# pmod-level-conv-vqfn.net
KiCad netlist of a schematic drawn in EAGLE
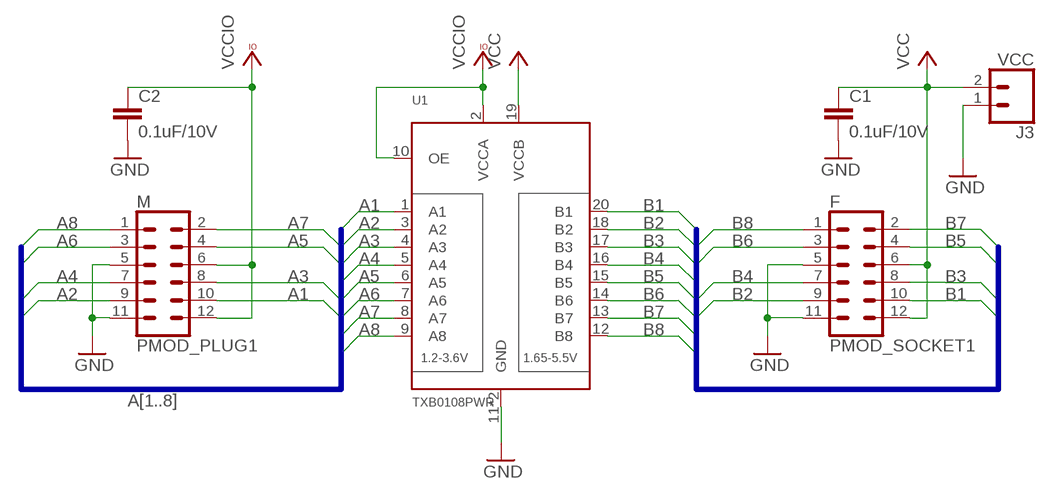
[diagram p0: schematic, sheet 1]

(export (version "E")
  (design (tool "Eeschema 10.0.6"))
  (components
    (comp (ref "C1")
      (value "0.1uF/10V")
      (footprint "eagle-import:C0603K")
      (libsource (lib "eagle-import") (part "C-EUC0603K"))
    )
    (comp (ref "C2")
      (value "0.1uF/10V")
      (footprint "eagle-import:C0603K")
      (libsource (lib "eagle-import") (part "C-EUC0603K"))
    )
    (comp (ref "F")
      (value "PMOD_SOCKET1")
      (footprint "eagle-import:2X6_SMD_RA_SOCKET")
      (libsource (lib "eagle-import") (part "CONN_06X2SMD_RA_SOCKET"))
    )
    (comp (ref "J3")
      (value "VCC")
      (footprint "eagle-import:JST-2-SMD")
      (libsource (lib "eagle-import") (part "CONN_02-JST-2MM-SMT"))
    )
    (comp (ref "M")
      (value "PMOD_PLUG1")
      (footprint "eagle-import:2X6_SMD_RA_PLUG")
      (libsource (lib "eagle-import") (part "CONN_06X2SMD_RA_PLUG"))
    )
    (comp (ref "U1")
      (value "TXB0108PWR")
      (footprint "eagle-import:VQFN-20")
      (libsource (lib "eagle-import") (part "TXB0108PWRVQFN20"))
    )
  )
  (nets
    (net (code "1") (name "/A1") (class "Default")
      (node (ref "M") (pin "10") (pinfunction "10_10") (pintype "passive"))
      (node (ref "U1") (pin "1") (pinfunction "A1_1") (pintype "bidirectional"))
    )
    (net (code "2") (name "/A2") (class "Default")
      (node (ref "M") (pin "9") (pinfunction "9_9") (pintype "passive"))
      (node (ref "U1") (pin "3") (pinfunction "A2_3") (pintype "bidirectional"))
    )
    (net (code "3") (name "/A3") (class "Default")
      (node (ref "M") (pin "8") (pinfunction "8_8") (pintype "passive"))
      (node (ref "U1") (pin "4") (pinfunction "A3_4") (pintype "bidirectional"))
    )
    (net (code "4") (name "/A4") (class "Default")
      (node (ref "M") (pin "7") (pinfunction "7_7") (pintype "passive"))
      (node (ref "U1") (pin "5") (pinfunction "A4_5") (pintype "bidirectional"))
    )
    (net (code "5") (name "/A5") (class "Default")
      (node (ref "M") (pin "4") (pinfunction "4_4") (pintype "passive"))
      (node (ref "U1") (pin "6") (pinfunction "A5_6") (pintype "bidirectional"))
    )
    (net (code "6") (name "/A6") (class "Default")
      (node (ref "M") (pin "3") (pinfunction "3_3") (pintype "passive"))
      (node (ref "U1") (pin "7") (pinfunction "A6_7") (pintype "bidirectional"))
    )
    (net (code "7") (name "/A7") (class "Default")
      (node (ref "M") (pin "2") (pinfunction "2_2") (pintype "passive"))
      (node (ref "U1") (pin "8") (pinfunction "A7_8") (pintype "bidirectional"))
    )
    (net (code "8") (name "/A8") (class "Default")
      (node (ref "M") (pin "1") (pinfunction "1_1") (pintype "passive"))
      (node (ref "U1") (pin "9") (pinfunction "A8_9") (pintype "bidirectional"))
    )
    (net (code "10") (name "/B1") (class "Default")
      (node (ref "F") (pin "10") (pinfunction "10_10") (pintype "passive"))
      (node (ref "U1") (pin "20") (pinfunction "B1_20") (pintype "bidirectional"))
    )
    (net (code "11") (name "/B2") (class "Default")
      (node (ref "F") (pin "9") (pinfunction "9_9") (pintype "passive"))
      (node (ref "U1") (pin "18") (pinfunction "B2_18") (pintype "bidirectional"))
    )
    (net (code "12") (name "/B3") (class "Default")
      (node (ref "F") (pin "8") (pinfunction "8_8") (pintype "passive"))
      (node (ref "U1") (pin "17") (pinfunction "B3_17") (pintype "bidirectional"))
    )
    (net (code "13") (name "/B4") (class "Default")
      (node (ref "F") (pin "7") (pinfunction "7_7") (pintype "passive"))
      (node (ref "U1") (pin "16") (pinfunction "B4_16") (pintype "bidirectional"))
    )
    (net (code "14") (name "/B5") (class "Default")
      (node (ref "F") (pin "4") (pinfunction "4_4") (pintype "passive"))
      (node (ref "U1") (pin "15") (pinfunction "B5_15") (pintype "bidirectional"))
    )
    (net (code "15") (name "/B6") (class "Default")
      (node (ref "F") (pin "3") (pinfunction "3_3") (pintype "passive"))
      (node (ref "U1") (pin "14") (pinfunction "B6_14") (pintype "bidirectional"))
    )
    (net (code "16") (name "/B7") (class "Default")
      (node (ref "F") (pin "2") (pinfunction "2_2") (pintype "passive"))
      (node (ref "U1") (pin "13") (pinfunction "B7_13") (pintype "bidirectional"))
    )
    (net (code "17") (name "/B8") (class "Default")
      (node (ref "F") (pin "1") (pinfunction "1_1") (pintype "passive"))
      (node (ref "U1") (pin "12") (pinfunction "B8_12") (pintype "bidirectional"))
    )
    (net (code "18") (name "GND") (class "Default")
      (node (ref "C1") (pin "2") (pinfunction "2_2") (pintype "passive"))
      (node (ref "C2") (pin "2") (pinfunction "2_2") (pintype "passive"))
      (node (ref "F") (pin "11") (pinfunction "11_11") (pintype "passive"))
      (node (ref "F") (pin "5") (pinfunction "5_5") (pintype "passive"))
      (node (ref "J3") (pin "1") (pinfunction "2_1") (pintype "passive"))
      (node (ref "M") (pin "11") (pinfunction "11_11") (pintype "passive"))
      (node (ref "M") (pin "5") (pinfunction "5_5") (pintype "passive"))
      (node (ref "U1") (pin "11") (pinfunction "GND_11") (pintype "bidirectional"))
      (node (ref "U1") (pin "PAD") (pinfunction "GND_PAD") (pintype "bidirectional"))
    )
    (net (code "19") (name "VCC") (class "Default")
      (node (ref "C1") (pin "1") (pinfunction "1_1") (pintype "passive"))
      (node (ref "F") (pin "12") (pinfunction "12_12") (pintype "passive"))
      (node (ref "F") (pin "6") (pinfunction "6_6") (pintype "passive"))
      (node (ref "J3") (pin "2") (pinfunction "1_2") (pintype "passive"))
      (node (ref "U1") (pin "19") (pinfunction "VCCB_19") (pintype "bidirectional"))
    )
    (net (code "20") (name "VCCIO") (class "Default")
      (node (ref "C2") (pin "1") (pinfunction "1_1") (pintype "passive"))
      (node (ref "M") (pin "12") (pinfunction "12_12") (pintype "passive"))
      (node (ref "M") (pin "6") (pinfunction "6_6") (pintype "passive"))
      (node (ref "U1") (pin "10") (pinfunction "OE_10") (pintype "bidirectional"))
      (node (ref "U1") (pin "2") (pinfunction "VCCA_2") (pintype "bidirectional"))
    )
  )
)
